# sells.net
KiCad netlist of a schematic drawn in EAGLE
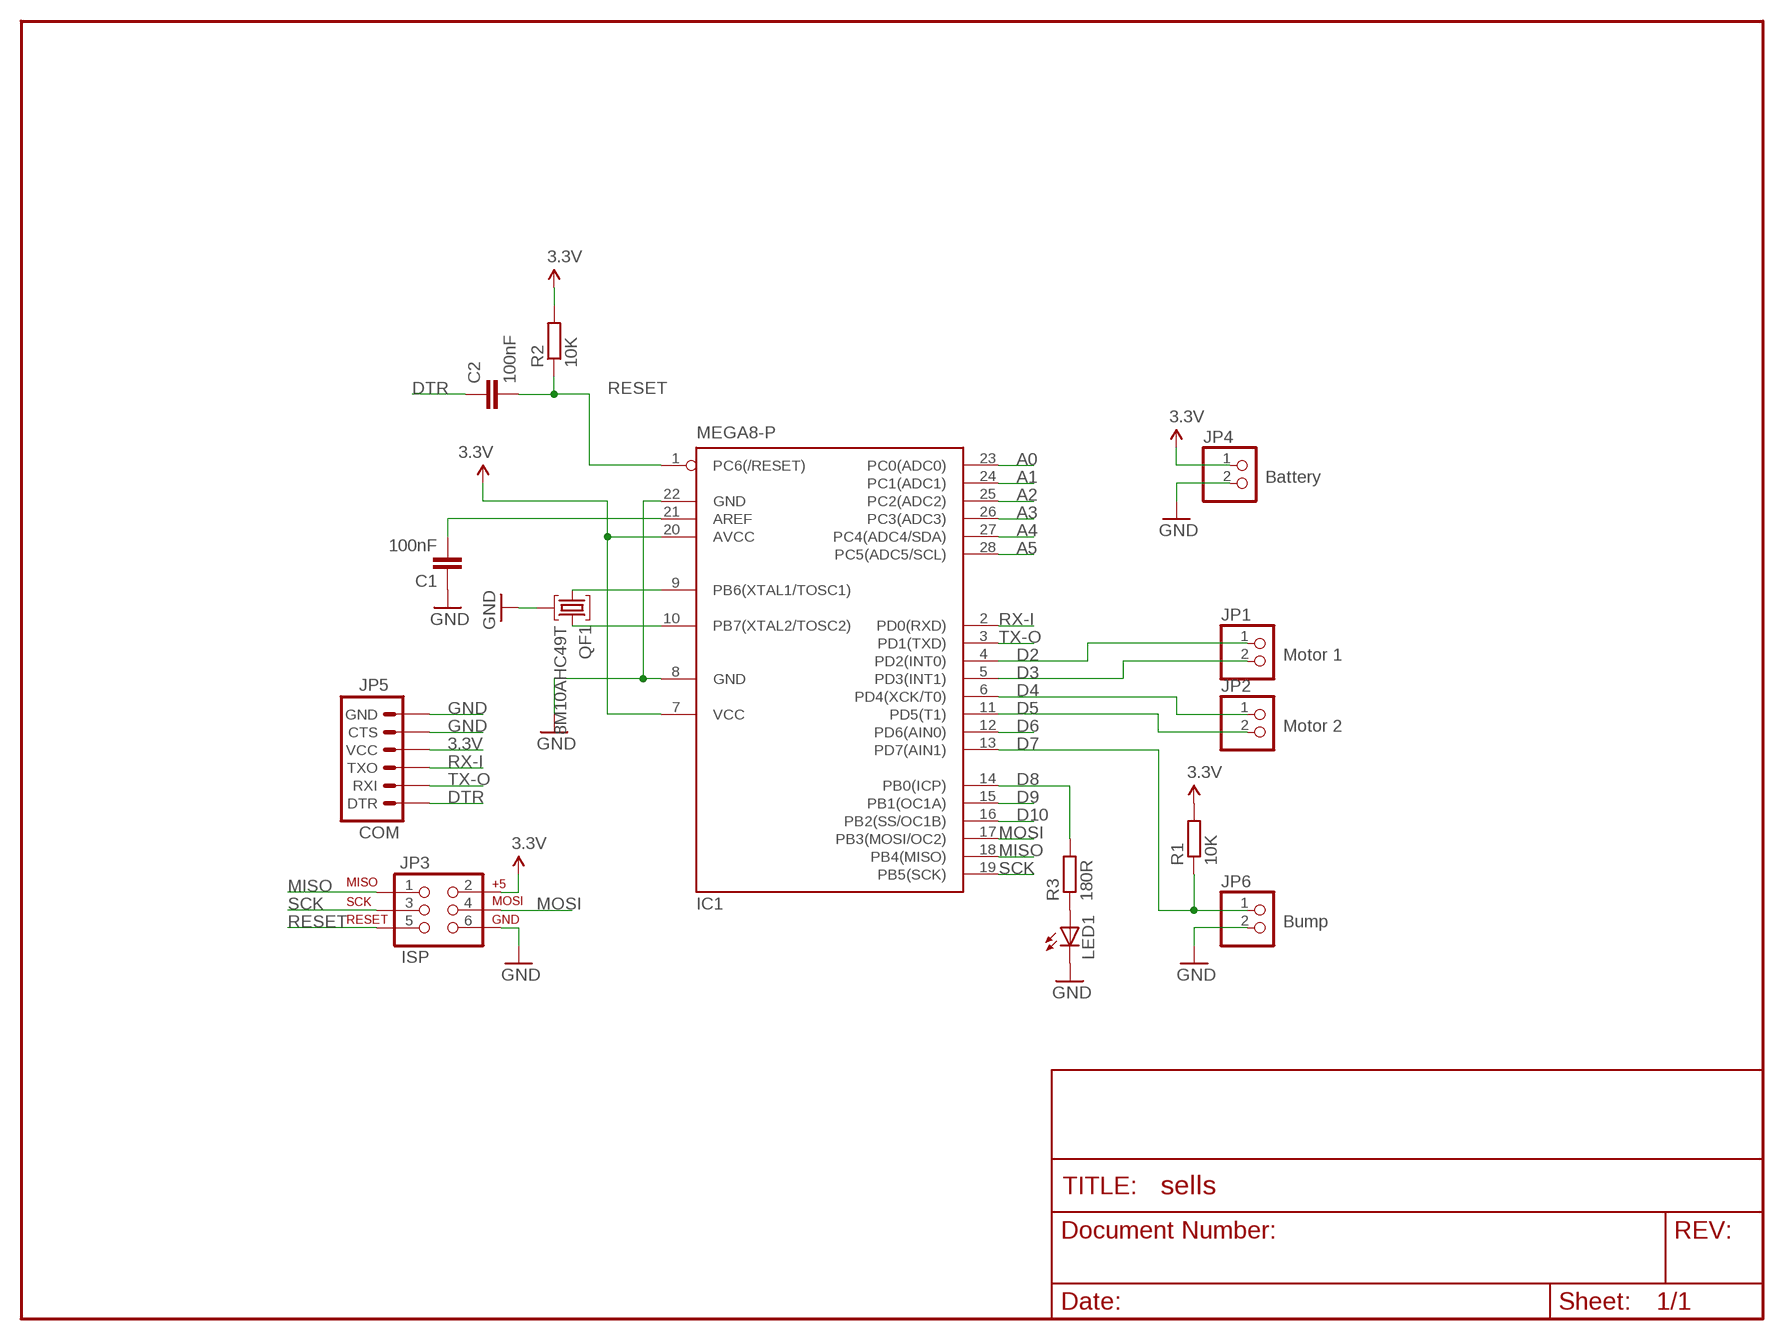
[diagram p0: schematic, sheet 1]

(export (version "E")
  (design (tool "Eeschema 10.0.6"))
  (components
    (comp (ref "C1")
      (value "100nF")
      (footprint "eagle-import:C050-050X075")
      (libsource (lib "eagle-import") (part "C-EU050-050X075"))
    )
    (comp (ref "C2")
      (value "100nF")
      (footprint "eagle-import:C050-050X075")
      (libsource (lib "eagle-import") (part "C-EU050-050X075"))
    )
    (comp (ref "IC1")
      (value "MEGA8-P")
      (footprint "eagle-import:DIL28-3")
      (libsource (lib "eagle-import") (part "MEGA8-P"))
    )
    (comp (ref "JP1")
      (value "PINHD-1X2")
      (footprint "eagle-import:1X02")
      (libsource (lib "eagle-import") (part "PINHD-1X2"))
    )
    (comp (ref "JP2")
      (value "PINHD-1X2")
      (footprint "eagle-import:1X02")
      (libsource (lib "eagle-import") (part "PINHD-1X2"))
    )
    (comp (ref "JP3")
      (value "ISP")
      (footprint "eagle-import:2X3")
      (libsource (lib "eagle-import") (part "AVR_SPI_PRG_6PTH"))
    )
    (comp (ref "JP4")
      (value "PINHD-1X2")
      (footprint "eagle-import:1X02")
      (libsource (lib "eagle-import") (part "PINHD-1X2"))
    )
    (comp (ref "JP5")
      (value "COM")
      (footprint "eagle-import:1X06")
      (libsource (lib "eagle-import") (part "ARDUINO_SERIAL_PROGRAMPTH"))
    )
    (comp (ref "JP6")
      (value "PINHD-1X2")
      (footprint "eagle-import:1X02")
      (libsource (lib "eagle-import") (part "PINHD-1X2"))
    )
    (comp (ref "LED1")
      (value "LED3MM")
      (footprint "eagle-import:LED3MM")
      (libsource (lib "eagle-import") (part "LED3MM"))
    )
    (comp (ref "QF1")
      (value "8M10AHC49T")
      (footprint "eagle-import:HC49U")
      (libsource (lib "eagle-import") (part "8M10AHC49T"))
    )
    (comp (ref "R1")
      (value "10K")
      (footprint "eagle-import:0207_10")
      (libsource (lib "eagle-import") (part "R-EU_0207/10"))
    )
    (comp (ref "R2")
      (value "10K")
      (footprint "eagle-import:0207_10")
      (libsource (lib "eagle-import") (part "R-EU_0207/10"))
    )
    (comp (ref "R3")
      (value "180R")
      (footprint "eagle-import:0207_10")
      (libsource (lib "eagle-import") (part "R-EU_0207/10"))
    )
  )
  (nets
    (net (code "1") (name "/A0") (class "Default")
      (node (ref "IC1") (pin "23") (pinfunction "PC0(ADC0)_23") (pintype "bidirectional"))
    )
    (net (code "2") (name "/A1") (class "Default")
      (node (ref "IC1") (pin "24") (pinfunction "PC1(ADC1)_24") (pintype "bidirectional"))
    )
    (net (code "3") (name "/A2") (class "Default")
      (node (ref "IC1") (pin "25") (pinfunction "PC2(ADC2)_25") (pintype "bidirectional"))
    )
    (net (code "4") (name "/A3") (class "Default")
      (node (ref "IC1") (pin "26") (pinfunction "PC3(ADC3)_26") (pintype "bidirectional"))
    )
    (net (code "5") (name "/A4") (class "Default")
      (node (ref "IC1") (pin "27") (pinfunction "PC4(ADC4/SDA)_27") (pintype "bidirectional"))
    )
    (net (code "6") (name "/A5") (class "Default")
      (node (ref "IC1") (pin "28") (pinfunction "PC5(ADC5/SCL)_28") (pintype "bidirectional"))
    )
    (net (code "7") (name "/D2") (class "Default")
      (node (ref "IC1") (pin "4") (pinfunction "PD2(INT0)_4") (pintype "bidirectional"))
      (node (ref "JP1") (pin "1") (pinfunction "1_1") (pintype "passive"))
    )
    (net (code "8") (name "/D3") (class "Default")
      (node (ref "IC1") (pin "5") (pinfunction "PD3(INT1)_5") (pintype "bidirectional"))
      (node (ref "JP1") (pin "2") (pinfunction "2_2") (pintype "passive"))
    )
    (net (code "9") (name "/D4") (class "Default")
      (node (ref "IC1") (pin "6") (pinfunction "PD4(XCK/T0)_6") (pintype "bidirectional"))
      (node (ref "JP2") (pin "1") (pinfunction "1_1") (pintype "passive"))
    )
    (net (code "10") (name "/D5") (class "Default")
      (node (ref "IC1") (pin "11") (pinfunction "PD5(T1)_11") (pintype "bidirectional"))
      (node (ref "JP2") (pin "2") (pinfunction "2_2") (pintype "passive"))
    )
    (net (code "11") (name "/D6") (class "Default")
      (node (ref "IC1") (pin "12") (pinfunction "PD6(AIN0)_12") (pintype "bidirectional"))
    )
    (net (code "12") (name "/D7") (class "Default")
      (node (ref "IC1") (pin "13") (pinfunction "PD7(AIN1)_13") (pintype "bidirectional"))
      (node (ref "JP6") (pin "1") (pinfunction "1_1") (pintype "passive"))
      (node (ref "R1") (pin "1") (pinfunction "1_1") (pintype "passive"))
    )
    (net (code "13") (name "/D8") (class "Default")
      (node (ref "IC1") (pin "14") (pinfunction "PB0(ICP)_14") (pintype "bidirectional"))
      (node (ref "R3") (pin "2") (pinfunction "2_2") (pintype "passive"))
    )
    (net (code "14") (name "/D9") (class "Default")
      (node (ref "IC1") (pin "15") (pinfunction "PB1(OC1A)_15") (pintype "bidirectional"))
    )
    (net (code "15") (name "/D10") (class "Default")
      (node (ref "IC1") (pin "16") (pinfunction "PB2(SS/OC1B)_16") (pintype "bidirectional"))
    )
    (net (code "16") (name "/DTR") (class "Default")
      (node (ref "C2") (pin "1") (pinfunction "1_1") (pintype "passive"))
      (node (ref "JP5") (pin "1") (pinfunction "DTR_1") (pintype "passive"))
    )
    (net (code "17") (name "/MISO") (class "Default")
      (node (ref "IC1") (pin "18") (pinfunction "PB4(MISO)_18") (pintype "bidirectional"))
      (node (ref "JP3") (pin "1") (pinfunction "1_1") (pintype "passive"))
    )
    (net (code "18") (name "/MOSI") (class "Default")
      (node (ref "IC1") (pin "17") (pinfunction "PB3(MOSI/OC2)_17") (pintype "bidirectional"))
      (node (ref "JP3") (pin "4") (pinfunction "4_4") (pintype "passive"))
    )
    (net (code "19") (name "/RESET") (class "Default")
      (node (ref "C2") (pin "2") (pinfunction "2_2") (pintype "passive"))
      (node (ref "IC1") (pin "1") (pinfunction "PC6(/RESET)_1") (pintype "bidirectional"))
      (node (ref "JP3") (pin "5") (pinfunction "5_5") (pintype "passive"))
      (node (ref "R2") (pin "1") (pinfunction "1_1") (pintype "passive"))
    )
    (net (code "20") (name "/RX-I") (class "Default")
      (node (ref "IC1") (pin "2") (pinfunction "PD0(RXD)_2") (pintype "bidirectional"))
      (node (ref "JP5") (pin "3") (pinfunction "TXO_3") (pintype "passive"))
    )
    (net (code "21") (name "/SCK") (class "Default")
      (node (ref "IC1") (pin "19") (pinfunction "PB5(SCK)_19") (pintype "bidirectional"))
      (node (ref "JP3") (pin "3") (pinfunction "3_3") (pintype "passive"))
    )
    (net (code "22") (name "/TX-O") (class "Default")
      (node (ref "IC1") (pin "3") (pinfunction "PD1(TXD)_3") (pintype "bidirectional"))
      (node (ref "JP5") (pin "2") (pinfunction "RXI_2") (pintype "passive"))
    )
    (net (code "23") (name "3.3V") (class "Default")
      (node (ref "IC1") (pin "20") (pinfunction "AVCC_20") (pintype "power_in"))
      (node (ref "IC1") (pin "7") (pinfunction "VCC_7") (pintype "power_in"))
      (node (ref "JP3") (pin "2") (pinfunction "2_2") (pintype "passive"))
      (node (ref "JP4") (pin "1") (pinfunction "1_1") (pintype "passive"))
      (node (ref "JP5") (pin "4") (pinfunction "VCC_4") (pintype "passive"))
      (node (ref "R1") (pin "2") (pinfunction "2_2") (pintype "passive"))
      (node (ref "R2") (pin "2") (pinfunction "2_2") (pintype "passive"))
    )
    (net (code "24") (name "GND") (class "Default")
      (node (ref "C1") (pin "1") (pinfunction "1_1") (pintype "passive"))
      (node (ref "IC1") (pin "22") (pinfunction "GND_22") (pintype "power_in"))
      (node (ref "IC1") (pin "8") (pinfunction "GND_8") (pintype "power_in"))
      (node (ref "JP3") (pin "6") (pinfunction "6_6") (pintype "passive"))
      (node (ref "JP4") (pin "2") (pinfunction "2_2") (pintype "passive"))
      (node (ref "JP5") (pin "5") (pinfunction "CTS_5") (pintype "passive"))
      (node (ref "JP5") (pin "6") (pinfunction "GND_6") (pintype "passive"))
      (node (ref "JP6") (pin "2") (pinfunction "2_2") (pintype "passive"))
      (node (ref "LED1") (pin "K") (pinfunction "C_K") (pintype "passive"))
      (node (ref "QF1") (pin "2") (pinfunction "2_2") (pintype "passive"))
    )
    (net (code "25") (name "Net-(IC1-AREF)") (class "Default")
      (node (ref "C1") (pin "2") (pinfunction "2_2") (pintype "passive"))
      (node (ref "IC1") (pin "21") (pinfunction "AREF_21") (pintype "passive"))
    )
    (net (code "26") (name "Net-(IC1-PB6(XTAL1{slash}TOSC1))") (class "Default")
      (node (ref "IC1") (pin "9") (pinfunction "PB6(XTAL1/TOSC1)_9") (pintype "bidirectional"))
      (node (ref "QF1") (pin "1") (pinfunction "1_1") (pintype "passive"))
    )
    (net (code "27") (name "Net-(IC1-PB7(XTAL2{slash}TOSC2))") (class "Default")
      (node (ref "IC1") (pin "10") (pinfunction "PB7(XTAL2/TOSC2)_10") (pintype "bidirectional"))
      (node (ref "QF1") (pin "3") (pinfunction "3_3") (pintype "passive"))
    )
    (net (code "28") (name "Net-(LED1-PadA)") (class "Default")
      (node (ref "LED1") (pin "A") (pinfunction "A_A") (pintype "passive"))
      (node (ref "R3") (pin "1") (pinfunction "1_1") (pintype "passive"))
    )
  )
)
